# dawa_v5_1.net
KiCad netlist of a schematic drawn in EAGLE
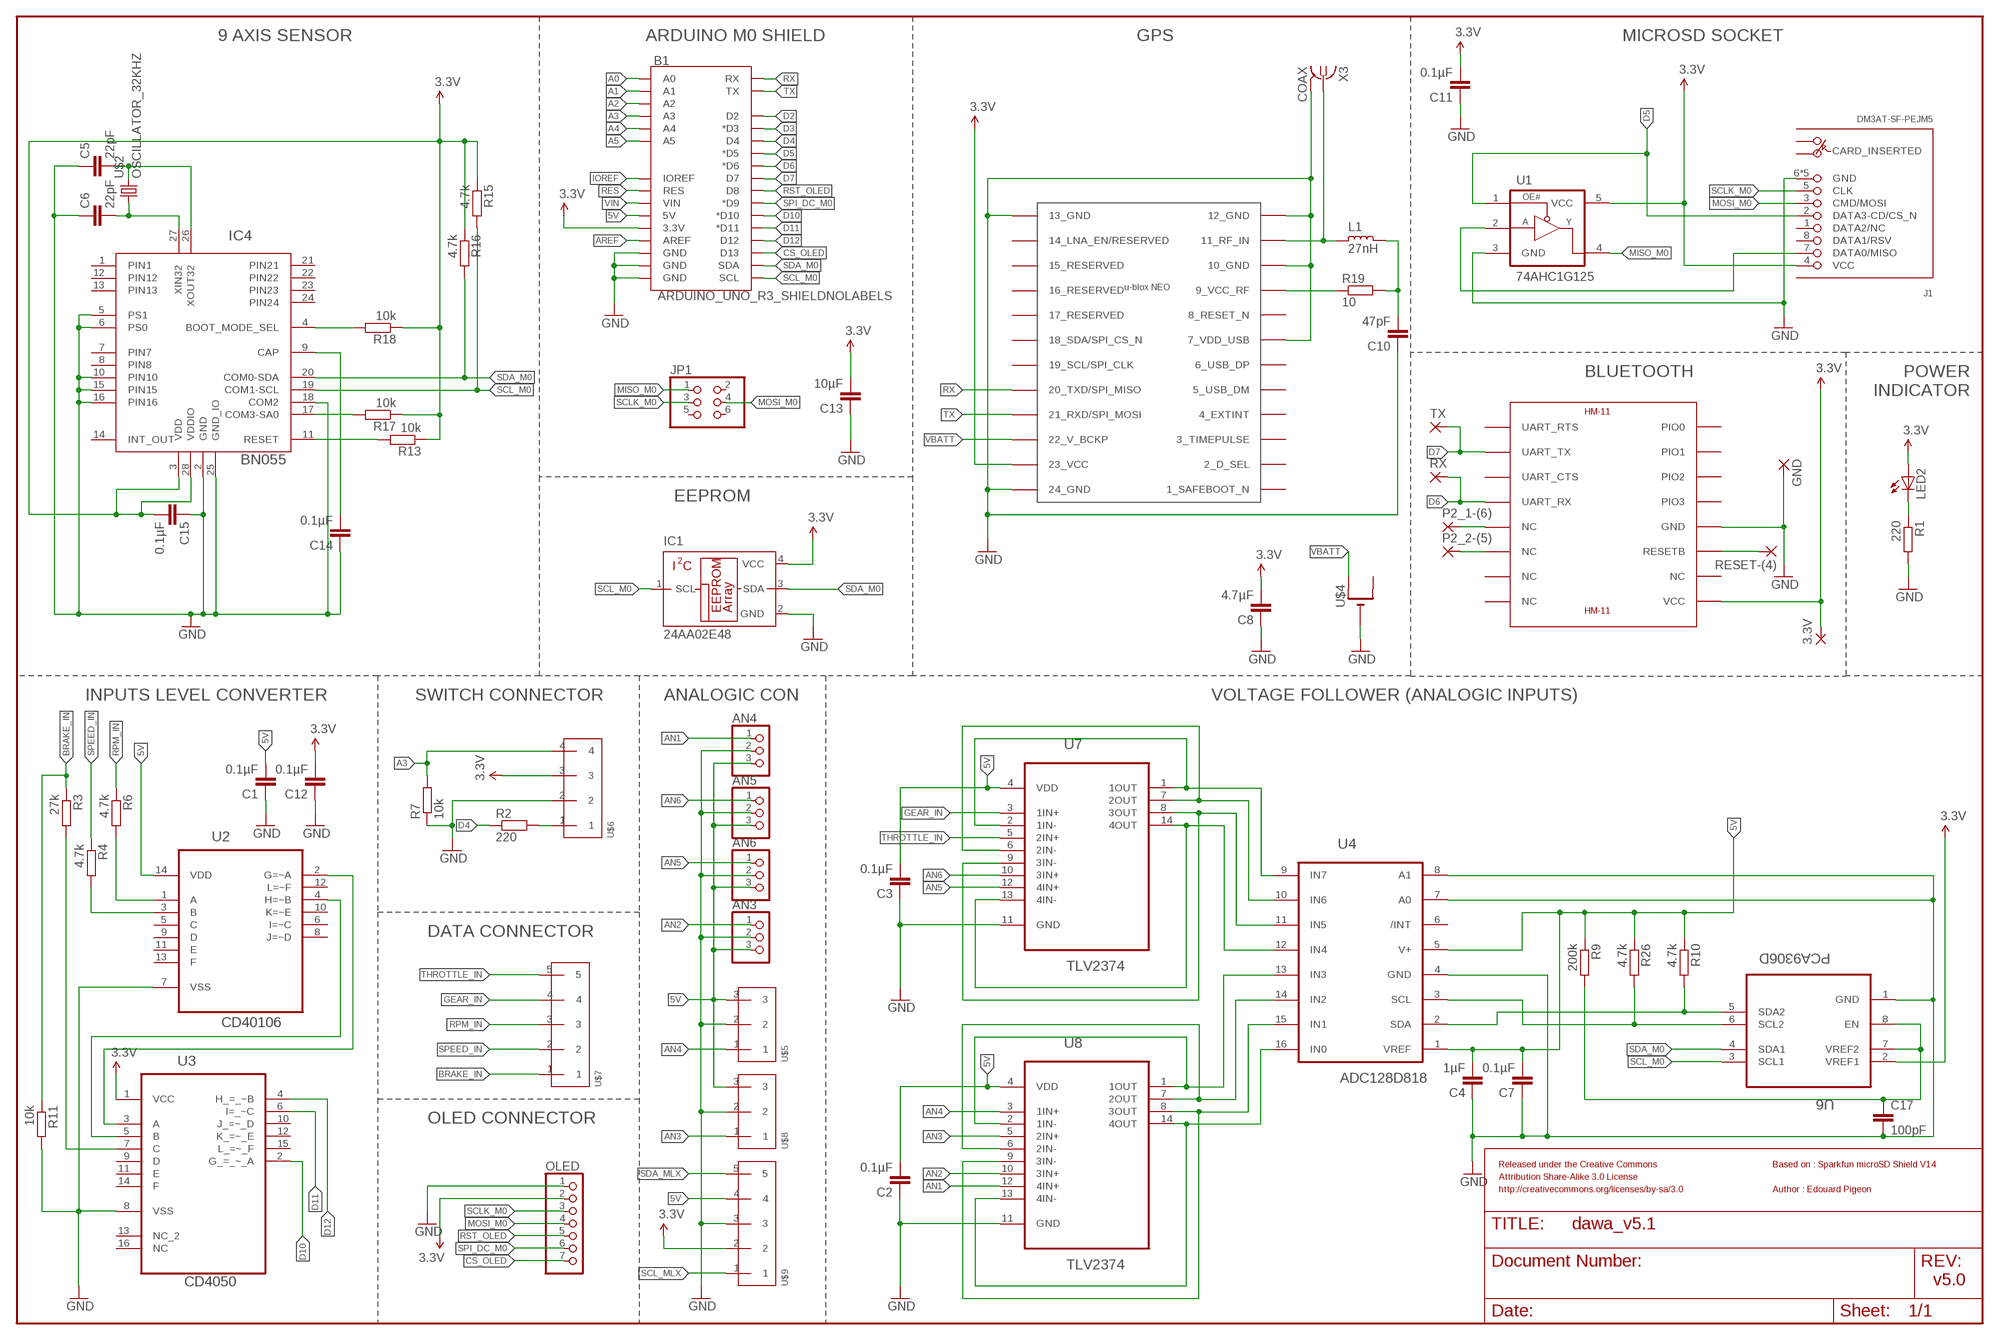
[diagram p0: schematic, sheet 1, part 1 of 2]
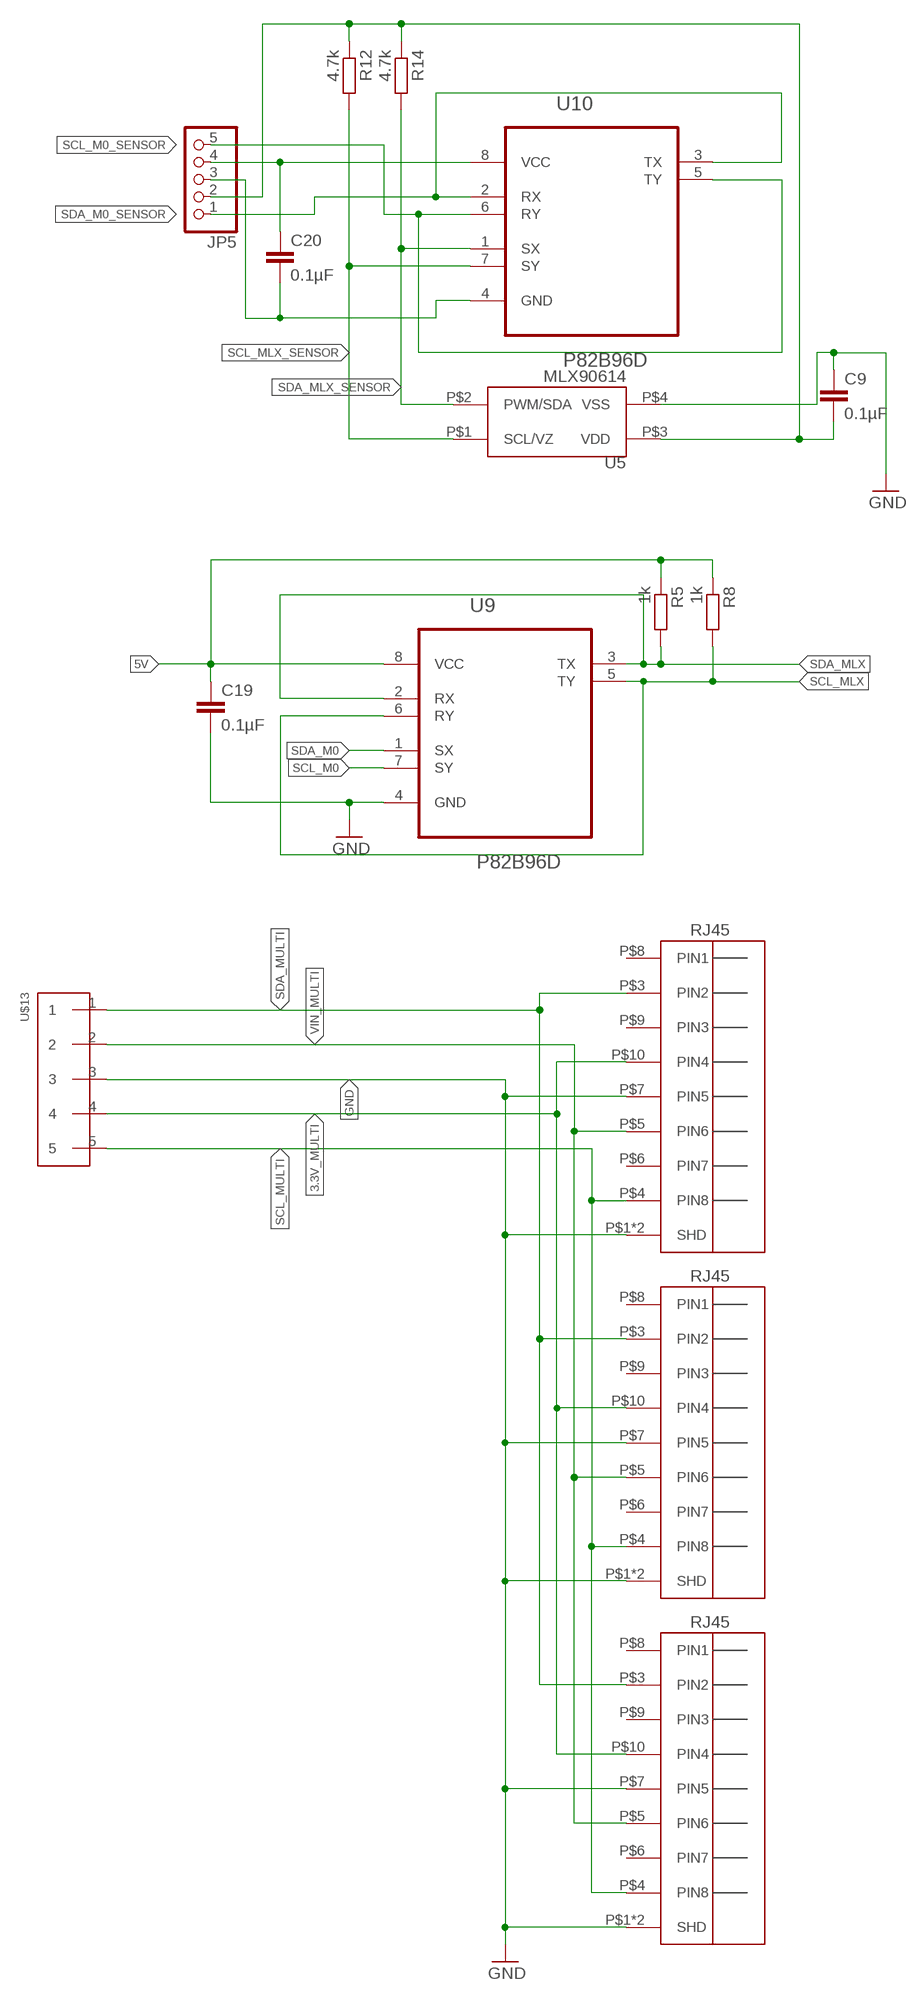
[diagram p1: schematic, sheet 1, part 2 of 2]

(export (version "E")
  (design (tool "Eeschema 10.0.6"))
  (components
    (comp (ref "3.3V")
      (value "WIREPADSMD1,27-254")
      (footprint "eagle-import:SMD1,27-2,54")
      (libsource (lib "eagle-import") (part "WIREPADSMD1,27-254"))
    )
    (comp (ref "AN3")
      (value "PINHD-1X3")
      (footprint "eagle-import:1X03")
      (libsource (lib "eagle-import") (part "PINHD-1X3"))
    )
    (comp (ref "AN4")
      (value "PINHD-1X3")
      (footprint "eagle-import:1X03")
      (libsource (lib "eagle-import") (part "PINHD-1X3"))
    )
    (comp (ref "AN5")
      (value "PINHD-1X3")
      (footprint "eagle-import:1X03")
      (libsource (lib "eagle-import") (part "PINHD-1X3"))
    )
    (comp (ref "AN6")
      (value "PINHD-1X3")
      (footprint "eagle-import:1X03")
      (libsource (lib "eagle-import") (part "PINHD-1X3"))
    )
    (comp (ref "B1")
      (value "ARDUINO_UNO_R3_SHIELDNOLABELS")
      (footprint "eagle-import:UNO_R3_SHIELD_NOLABELS")
      (libsource (lib "eagle-import") (part "ARDUINO_UNO_R3_SHIELDNOLABELS"))
    )
    (comp (ref "C1")
      (value "0.1µF")
      (footprint "eagle-import:C0603")
      (libsource (lib "eagle-import") (part "C-EUC0603"))
    )
    (comp (ref "C2")
      (value "0.1µF")
      (footprint "eagle-import:C0603")
      (libsource (lib "eagle-import") (part "C-EUC0603"))
    )
    (comp (ref "C3")
      (value "0.1µF")
      (footprint "eagle-import:C0603")
      (libsource (lib "eagle-import") (part "C-EUC0603"))
    )
    (comp (ref "C4")
      (value "1µF")
      (footprint "eagle-import:C0603")
      (libsource (lib "eagle-import") (part "C-EUC0603"))
    )
    (comp (ref "C5")
      (value "22pF")
      (footprint "eagle-import:C0603")
      (libsource (lib "eagle-import") (part "C-EUC0603"))
    )
    (comp (ref "C6")
      (value "22pF")
      (footprint "eagle-import:C0603")
      (libsource (lib "eagle-import") (part "C-EUC0603"))
    )
    (comp (ref "C7")
      (value "0.1µF")
      (footprint "eagle-import:C0603")
      (libsource (lib "eagle-import") (part "C-EUC0603"))
    )
    (comp (ref "C8")
      (value "4.7µF")
      (footprint "eagle-import:C0603")
      (libsource (lib "eagle-import") (part "C-EUC0603"))
    )
    (comp (ref "C9")
      (value "0.1µF")
      (footprint "eagle-import:C0603")
      (libsource (lib "eagle-import") (part "C-EUC0603"))
    )
    (comp (ref "C10")
      (value "47pF")
      (footprint "eagle-import:C0603")
      (libsource (lib "eagle-import") (part "C-EUC0603"))
    )
    (comp (ref "C11")
      (value "0.1µF")
      (footprint "eagle-import:C0603")
      (libsource (lib "eagle-import") (part "C-EUC0603"))
    )
    (comp (ref "C12")
      (value "0.1µF")
      (footprint "eagle-import:C0603")
      (libsource (lib "eagle-import") (part "C-EUC0603"))
    )
    (comp (ref "C13")
      (value "10µF")
      (footprint "eagle-import:C0603")
      (libsource (lib "eagle-import") (part "C-EUC0603"))
    )
    (comp (ref "C14")
      (value "0.1µF")
      (footprint "eagle-import:C0603")
      (libsource (lib "eagle-import") (part "C-EUC0603"))
    )
    (comp (ref "C15")
      (value "0.1µF")
      (footprint "eagle-import:C0603")
      (libsource (lib "eagle-import") (part "C-EUC0603"))
    )
    (comp (ref "C17")
      (value "100pF")
      (footprint "eagle-import:C0603")
      (libsource (lib "eagle-import") (part "C-EUC0603"))
    )
    (comp (ref "C19")
      (value "0.1µF")
      (footprint "eagle-import:C0603")
      (libsource (lib "eagle-import") (part "C-EUC0603"))
    )
    (comp (ref "C20")
      (value "0.1µF")
      (footprint "eagle-import:C0603")
      (libsource (lib "eagle-import") (part "C-EUC0603"))
    )
    (comp (ref "GND")
      (value "WIREPADSMD1,27-254")
      (footprint "eagle-import:SMD1,27-2,54")
      (libsource (lib "eagle-import") (part "WIREPADSMD1,27-254"))
    )
    (comp (ref "IC1")
      (value "24AA02E48")
      (footprint "eagle-import:SOT23-5L")
      (fields (field (name "MF") "MICROCHIP") (field (name "MPN") "24AA00T-I/OTG"))
      (libsource (lib "eagle-import") (part "2400OTAA"))
    )
    (comp (ref "IC4")
      (value "BN055")
      (footprint "eagle-import:LGA-28_3.80X5.20_0.5")
      (fields (field (name "PART_NUMBER") "BNO055"))
      (libsource (lib "eagle-import") (part "1658_BNO055"))
    )
    (comp (ref "J1")
      (value "DM3AT-SF-PEJM5")
      (footprint "eagle-import:DM3AT-SF-PEJM5")
      (libsource (lib "eagle-import") (part "DM3AT-SF-PEJM5"))
    )
    (comp (ref "JP1")
      (value "PINHD-2X3")
      (footprint "eagle-import:2X03")
      (libsource (lib "eagle-import") (part "PINHD-2X3"))
    )
    (comp (ref "JP5")
      (value "PINHD-1X5")
      (footprint "eagle-import:1X05")
      (libsource (lib "eagle-import") (part "PINHD-1X5"))
    )
    (comp (ref "L1")
      (value "27nH")
      (footprint "eagle-import:L0603")
      (libsource (lib "eagle-import") (part "L_0603"))
    )
    (comp (ref "LED2")
      (value "LEDCHIPLED_1206")
      (footprint "eagle-import:CHIPLED_1206")
      (libsource (lib "eagle-import") (part "LEDCHIPLED_1206"))
    )
    (comp (ref "OLED")
      (value "PINHD-1X7")
      (footprint "eagle-import:1X07")
      (libsource (lib "eagle-import") (part "PINHD-1X7"))
    )
    (comp (ref "P2_1-(6)")
      (value "WIREPADSMD1,27-254")
      (footprint "eagle-import:SMD1,27-2,54")
      (libsource (lib "eagle-import") (part "WIREPADSMD1,27-254"))
    )
    (comp (ref "P2_2-(5)")
      (value "WIREPADSMD1,27-254")
      (footprint "eagle-import:SMD1,27-2,54")
      (libsource (lib "eagle-import") (part "WIREPADSMD1,27-254"))
    )
    (comp (ref "R1")
      (value "220")
      (footprint "eagle-import:R0603")
      (libsource (lib "eagle-import") (part "R-EU_R0603"))
    )
    (comp (ref "R2")
      (value "220")
      (footprint "eagle-import:R0603")
      (libsource (lib "eagle-import") (part "R-EU_R0603"))
    )
    (comp (ref "R3")
      (value "27k")
      (footprint "eagle-import:R0603")
      (libsource (lib "eagle-import") (part "R-EU_R0603"))
    )
    (comp (ref "R4")
      (value "4.7k")
      (footprint "eagle-import:R0603")
      (libsource (lib "eagle-import") (part "R-EU_R0603"))
    )
    (comp (ref "R5")
      (value "1k")
      (footprint "eagle-import:R0603")
      (libsource (lib "eagle-import") (part "R-EU_R0603"))
    )
    (comp (ref "R6")
      (value "4.7k")
      (footprint "eagle-import:R0603")
      (libsource (lib "eagle-import") (part "R-EU_R0603"))
    )
    (comp (ref "R7")
      (value "10k")
      (footprint "eagle-import:R0603")
      (libsource (lib "eagle-import") (part "R-EU_R0603"))
    )
    (comp (ref "R8")
      (value "1k")
      (footprint "eagle-import:R0603")
      (libsource (lib "eagle-import") (part "R-EU_R0603"))
    )
    (comp (ref "R9")
      (value "200k")
      (footprint "eagle-import:R0603")
      (libsource (lib "eagle-import") (part "R-EU_R0603"))
    )
    (comp (ref "R10")
      (value "4.7k")
      (footprint "eagle-import:R0603")
      (libsource (lib "eagle-import") (part "R-EU_R0603"))
    )
    (comp (ref "R11")
      (value "10k")
      (footprint "eagle-import:R0603")
      (libsource (lib "eagle-import") (part "R-EU_R0603"))
    )
    (comp (ref "R12")
      (value "4.7k")
      (footprint "eagle-import:R0603")
      (libsource (lib "eagle-import") (part "R-EU_R0603"))
    )
    (comp (ref "R13")
      (value "10k")
      (footprint "eagle-import:R0603")
      (libsource (lib "eagle-import") (part "R-EU_R0603"))
    )
    (comp (ref "R14")
      (value "4.7k")
      (footprint "eagle-import:R0603")
      (libsource (lib "eagle-import") (part "R-EU_R0603"))
    )
    (comp (ref "R15")
      (value "4.7k")
      (footprint "eagle-import:R0603")
      (libsource (lib "eagle-import") (part "R-EU_R0603"))
    )
    (comp (ref "R16")
      (value "4.7k")
      (footprint "eagle-import:R0603")
      (libsource (lib "eagle-import") (part "R-EU_R0603"))
    )
    (comp (ref "R17")
      (value "10k")
      (footprint "eagle-import:R0603")
      (libsource (lib "eagle-import") (part "R-EU_R0603"))
    )
    (comp (ref "R18")
      (value "10k")
      (footprint "eagle-import:R0603")
      (libsource (lib "eagle-import") (part "R-EU_R0603"))
    )
    (comp (ref "R19")
      (value "10")
      (footprint "eagle-import:M1206")
      (libsource (lib "eagle-import") (part "R-EU_M1206"))
    )
    (comp (ref "R26")
      (value "4.7k")
      (footprint "eagle-import:R0603")
      (libsource (lib "eagle-import") (part "R-EU_R0603"))
    )
    (comp (ref "RESET-(4)")
      (value "WIREPADSMD1,27-254")
      (footprint "eagle-import:SMD1,27-2,54")
      (libsource (lib "eagle-import") (part "WIREPADSMD1,27-254"))
    )
    (comp (ref "RX")
      (value "WIREPADSMD1,27-254")
      (footprint "eagle-import:SMD1,27-2,54")
      (libsource (lib "eagle-import") (part "WIREPADSMD1,27-254"))
    )
    (comp (ref "TX")
      (value "WIREPADSMD1,27-254")
      (footprint "eagle-import:SMD1,27-2,54")
      (libsource (lib "eagle-import") (part "WIREPADSMD1,27-254"))
    )
    (comp (ref "U$1")
      (value "HM-11")
      (footprint "eagle-import:HM-11")
      (libsource (lib "eagle-import") (part "HM-11"))
    )
    (comp (ref "U$2")
      (value "OSCILLATOR_32KHZ")
      (footprint "eagle-import:OSCILLATOR_SMD")
      (libsource (lib "eagle-import") (part "OSCILLATOR_32KHZ"))
    )
    (comp (ref "U$3")
      (value "NEO-M8")
      (footprint "eagle-import:NEO-M8")
      (libsource (lib "eagle-import") (part "NEO-M8"))
    )
    (comp (ref "U$4")
      (value "CR1220SMT")
      (footprint "eagle-import:CR1220-SMD")
      (libsource (lib "eagle-import") (part "CR1220SMT"))
    )
    (comp (ref "U$5")
      (value "3_PIN_JST-XH-SMD")
      (footprint "eagle-import:3_PIN_JST-XH-SMD")
      (libsource (lib "eagle-import") (part "3_PIN_JST-XH-SMD"))
    )
    (comp (ref "U$6")
      (value "4_PIN_JST-XH-SMD")
      (footprint "eagle-import:4_PIN_JST-XH-SMD")
      (libsource (lib "eagle-import") (part "4_PIN_JST-XH-SMD"))
    )
    (comp (ref "U$7")
      (value "5_PIN_JST-XH-SMD")
      (footprint "eagle-import:5_PIN_JST-XH-SMD")
      (libsource (lib "eagle-import") (part "5_PIN_JST-XH-SMD"))
    )
    (comp (ref "U$8")
      (value "3_PIN_JST-XH-SMD")
      (footprint "eagle-import:3_PIN_JST-XH-SMD")
      (libsource (lib "eagle-import") (part "3_PIN_JST-XH-SMD"))
    )
    (comp (ref "U$9")
      (value "5_PIN_JST-XH-SMD")
      (footprint "eagle-import:5_PIN_JST-XH-SMD")
      (libsource (lib "eagle-import") (part "5_PIN_JST-XH-SMD"))
    )
    (comp (ref "U$10")
      (value "RJ45")
      (footprint "eagle-import:RJ45")
      (libsource (lib "eagle-import") (part "RJ45"))
    )
    (comp (ref "U$11")
      (value "RJ45")
      (footprint "eagle-import:RJ45")
      (libsource (lib "eagle-import") (part "RJ45"))
    )
    (comp (ref "U$12")
      (value "RJ45")
      (footprint "eagle-import:RJ45")
      (libsource (lib "eagle-import") (part "RJ45"))
    )
    (comp (ref "U$13")
      (value "5_PIN_JST-XH-SMD")
      (footprint "eagle-import:5_PIN_JST-XH-SMD")
      (libsource (lib "eagle-import") (part "5_PIN_JST-XH-SMD"))
    )
    (comp (ref "U1")
      (value "74AHC1G125")
      (footprint "eagle-import:SOT23-5")
      (libsource (lib "eagle-import") (part "74AHC1G125DBV"))
    )
    (comp (ref "U2")
      (value "CD40106")
      (footprint "eagle-import:SOP65P640X120-14N")
      (fields (field (name "MPN") "CD40106BPW"))
      (libsource (lib "eagle-import") (part "CD40106BPW"))
    )
    (comp (ref "U3")
      (value "CD4050")
      (footprint "eagle-import:SOP65P640X120-16N")
      (fields (field (name "MPN") "CD4049UBPW"))
      (libsource (lib "eagle-import") (part "CD4049UBPW"))
    )
    (comp (ref "U4")
      (value "ADC128D818")
      (footprint "eagle-import:SOP65P640X120-16N")
      (libsource (lib "eagle-import") (part "ADC128D818"))
    )
    (comp (ref "U5")
      (value "MLX90614")
      (footprint "eagle-import:TO-39")
      (libsource (lib "eagle-import") (part "MLX90614_"))
    )
    (comp (ref "U6")
      (value "PCA9306D")
      (footprint "eagle-import:SOP50P310X90-8N")
      (fields (field (name "MPN") "PCA9306DCUT"))
      (libsource (lib "eagle-import") (part "PCA9306DCUT"))
    )
    (comp (ref "U7")
      (value "TLV2374")
      (footprint "eagle-import:SOP65P640X120-14N")
      (fields (field (name "MPN") "TLV2374IPWR"))
      (libsource (lib "eagle-import") (part "TLV2374IPWR"))
    )
    (comp (ref "U8")
      (value "TLV2374")
      (footprint "eagle-import:SOP65P640X120-14N")
      (fields (field (name "MPN") "TLV2374IPWR"))
      (libsource (lib "eagle-import") (part "TLV2374IPWR"))
    )
    (comp (ref "U9")
      (value "P82B96D")
      (footprint "eagle-import:SOIC127P600X175-8N")
      (libsource (lib "eagle-import") (part "P82B96D"))
    )
    (comp (ref "U10")
      (value "P82B96D")
      (footprint "eagle-import:SOIC127P600X175-8N")
      (libsource (lib "eagle-import") (part "P82B96D"))
    )
    (comp (ref "X3")
      (value "COAX")
      (footprint "eagle-import:MMCX-J-P-X-ST-EM1-MKT")
      (libsource (lib "eagle-import") (part "COAX"))
    )
  )
  (nets
    (net (code "1") (name "3.3V") (class "Default")
      (node (ref "3.3V") (pin "1") (pinfunction "P_1") (pintype "passive"))
      (node (ref "B1") (pin "3.3V") (pinfunction "3.3V_3.3V") (pintype "bidirectional"))
      (node (ref "C11") (pin "2") (pinfunction "2_2") (pintype "passive"))
      (node (ref "C12") (pin "2") (pinfunction "2_2") (pintype "passive"))
      (node (ref "C13") (pin "2") (pinfunction "2_2") (pintype "passive"))
      (node (ref "C15") (pin "2") (pinfunction "2_2") (pintype "passive"))
      (node (ref "C8") (pin "2") (pinfunction "2_2") (pintype "passive"))
      (node (ref "IC1") (pin "4") (pinfunction "VCC_4") (pintype "power_in"))
      (node (ref "IC4") (pin "28") (pinfunction "VDDIO_28") (pintype "power_in"))
      (node (ref "IC4") (pin "3") (pinfunction "VDD_3") (pintype "power_in"))
      (node (ref "J1") (pin "4") (pinfunction "VCC_4") (pintype "bidirectional"))
      (node (ref "LED2") (pin "A") (pinfunction "A_A") (pintype "passive"))
      (node (ref "OLED") (pin "2") (pinfunction "2_2") (pintype "passive"))
      (node (ref "R13") (pin "1") (pinfunction "1_1") (pintype "passive"))
      (node (ref "R15") (pin "1") (pinfunction "1_1") (pintype "passive"))
      (node (ref "R16") (pin "1") (pinfunction "1_1") (pintype "passive"))
      (node (ref "R17") (pin "1") (pinfunction "1_1") (pintype "passive"))
      (node (ref "R18") (pin "1") (pinfunction "1_1") (pintype "passive"))
      (node (ref "U$1") (pin "VCC") (pinfunction "VCC_VCC") (pintype "bidirectional"))
      (node (ref "U$3") (pin "23") (pinfunction "23_VCC_23") (pintype "bidirectional"))
      (node (ref "U$6") (pin "3") (pinfunction "3_3") (pintype "bidirectional"))
      (node (ref "U$9") (pin "2") (pinfunction "2_2") (pintype "bidirectional"))
      (node (ref "U1") (pin "5") (pinfunction "VCC_5") (pintype "power_in"))
      (node (ref "U3") (pin "1") (pinfunction "VCC_1") (pintype "power_in"))
      (node (ref "U6") (pin "2") (pinfunction "VREF1_2") (pintype "power_in"))
    )
    (net (code "2") (name "3.3V_MULTI") (class "Default")
      (node (ref "U$10") (pin "P$10") (pinfunction "PIN4_P$10") (pintype "bidirectional"))
      (node (ref "U$11") (pin "P$10") (pinfunction "PIN4_P$10") (pintype "bidirectional"))
      (node (ref "U$12") (pin "P$10") (pinfunction "PIN4_P$10") (pintype "bidirectional"))
      (node (ref "U$13") (pin "4") (pinfunction "4_4") (pintype "bidirectional"))
    )
    (net (code "3") (name "5V") (class "Default")
      (node (ref "AN3") (pin "3") (pinfunction "3_3") (pintype "passive"))
      (node (ref "AN4") (pin "3") (pinfunction "3_3") (pintype "passive"))
      (node (ref "AN5") (pin "3") (pinfunction "3_3") (pintype "passive"))
      (node (ref "AN6") (pin "3") (pinfunction "3_3") (pintype "passive"))
      (node (ref "B1") (pin "5V") (pinfunction "5V_5V") (pintype "bidirectional"))
      (node (ref "C1") (pin "2") (pinfunction "2_2") (pintype "passive"))
      (node (ref "C19") (pin "1") (pinfunction "1_1") (pintype "passive"))
      (node (ref "C2") (pin "2") (pinfunction "2_2") (pintype "passive"))
      (node (ref "C3") (pin "2") (pinfunction "2_2") (pintype "passive"))
      (node (ref "C4") (pin "2") (pinfunction "2_2") (pintype "passive"))
      (node (ref "C7") (pin "2") (pinfunction "2_2") (pintype "passive"))
      (node (ref "R10") (pin "1") (pinfunction "1_1") (pintype "passive"))
      (node (ref "R26") (pin "1") (pinfunction "1_1") (pintype "passive"))
      (node (ref "R5") (pin "1") (pinfunction "1_1") (pintype "passive"))
      (node (ref "R8") (pin "1") (pinfunction "1_1") (pintype "passive"))
      (node (ref "R9") (pin "1") (pinfunction "1_1") (pintype "passive"))
      (node (ref "U$5") (pin "3") (pinfunction "3_3") (pintype "bidirectional"))
      (node (ref "U$8") (pin "3") (pinfunction "3_3") (pintype "bidirectional"))
      (node (ref "U$9") (pin "4") (pinfunction "4_4") (pintype "bidirectional"))
      (node (ref "U2") (pin "14") (pinfunction "VDD_14") (pintype "power_in"))
      (node (ref "U4") (pin "1") (pinfunction "VREF_1") (pintype "power_in"))
      (node (ref "U4") (pin "5") (pinfunction "V+_5") (pintype "bidirectional"))
      (node (ref "U7") (pin "4") (pinfunction "VDD_4") (pintype "power_in"))
      (node (ref "U8") (pin "4") (pinfunction "VDD_4") (pintype "power_in"))
      (node (ref "U9") (pin "8") (pinfunction "VCC_8") (pintype "power_in"))
    )
    (net (code "4") (name "A0") (class "Default")
      (node (ref "B1") (pin "A0") (pinfunction "A0_A0") (pintype "bidirectional"))
    )
    (net (code "5") (name "A1") (class "Default")
      (node (ref "B1") (pin "A1") (pinfunction "A1_A1") (pintype "bidirectional"))
    )
    (net (code "6") (name "A2") (class "Default")
      (node (ref "B1") (pin "A2") (pinfunction "A2_A2") (pintype "bidirectional"))
    )
    (net (code "7") (name "A3") (class "Default")
      (node (ref "B1") (pin "A3") (pinfunction "A3_A3") (pintype "bidirectional"))
      (node (ref "R7") (pin "2") (pinfunction "2_2") (pintype "passive"))
      (node (ref "U$6") (pin "4") (pinfunction "4_4") (pintype "bidirectional"))
    )
    (net (code "8") (name "A4") (class "Default")
      (node (ref "B1") (pin "A4") (pinfunction "A4_A4") (pintype "bidirectional"))
    )
    (net (code "9") (name "A5") (class "Default")
      (node (ref "B1") (pin "A5") (pinfunction "A5_A5") (pintype "bidirectional"))
    )
    (net (code "10") (name "AN1") (class "Default")
      (node (ref "AN4") (pin "1") (pinfunction "1_1") (pintype "passive"))
      (node (ref "U8") (pin "12") (pinfunction "4IN+_12") (pintype "input"))
    )
    (net (code "11") (name "AN2") (class "Default")
      (node (ref "AN3") (pin "1") (pinfunction "1_1") (pintype "passive"))
      (node (ref "U8") (pin "10") (pinfunction "3IN+_10") (pintype "input"))
    )
    (net (code "12") (name "AN3") (class "Default")
      (node (ref "U$8") (pin "1") (pinfunction "1_1") (pintype "bidirectional"))
      (node (ref "U8") (pin "5") (pinfunction "2IN+_5") (pintype "input"))
    )
    (net (code "13") (name "AN4") (class "Default")
      (node (ref "U$5") (pin "1") (pinfunction "1_1") (pintype "bidirectional"))
      (node (ref "U8") (pin "3") (pinfunction "1IN+_3") (pintype "input"))
    )
    (net (code "14") (name "AN5") (class "Default")
      (node (ref "AN6") (pin "1") (pinfunction "1_1") (pintype "passive"))
      (node (ref "U7") (pin "12") (pinfunction "4IN+_12") (pintype "input"))
    )
    (net (code "15") (name "AN6") (class "Default")
      (node (ref "AN5") (pin "1") (pinfunction "1_1") (pintype "passive"))
      (node (ref "U7") (pin "10") (pinfunction "3IN+_10") (pintype "input"))
    )
    (net (code "16") (name "AREF") (class "Default")
      (node (ref "B1") (pin "AREF") (pinfunction "AREF_AREF") (pintype "bidirectional"))
    )
    (net (code "17") (name "BRAKE_IN") (class "Default")
      (node (ref "R11") (pin "1") (pinfunction "1_1") (pintype "passive"))
      (node (ref "R3") (pin "1") (pinfunction "1_1") (pintype "passive"))
      (node (ref "U$7") (pin "1") (pinfunction "1_1") (pintype "bidirectional"))
    )
    (net (code "18") (name "CS_OLED") (class "Default")
      (node (ref "B1") (pin "D13") (pinfunction "D13_D13") (pintype "bidirectional"))
      (node (ref "OLED") (pin "7") (pinfunction "7_7") (pintype "passive"))
    )
    (net (code "19") (name "D2") (class "Default")
      (node (ref "B1") (pin "D2") (pinfunction "D2_D2") (pintype "bidirectional"))
    )
    (net (code "20") (name "D3") (class "Default")
      (node (ref "B1") (pin "D3") (pinfunction "*D3_D3") (pintype "bidirectional"))
    )
    (net (code "21") (name "D4") (class "Default")
      (node (ref "B1") (pin "D4") (pinfunction "D4_D4") (pintype "bidirectional"))
      (node (ref "R2") (pin "1") (pinfunction "1_1") (pintype "passive"))
    )
    (net (code "22") (name "D5") (class "Default")
      (node (ref "B1") (pin "D5") (pinfunction "*D5_D5") (pintype "bidirectional"))
      (node (ref "J1") (pin "2") (pinfunction "DATA3-CD/CS_N_2") (pintype "bidirectional"))
      (node (ref "U1") (pin "1") (pinfunction "OE#_1") (pintype "input"))
    )
    (net (code "23") (name "D6") (class "Default")
      (node (ref "B1") (pin "D6") (pinfunction "*D6_D6") (pintype "bidirectional"))
      (node (ref "RX") (pin "1") (pinfunction "P_1") (pintype "passive"))
      (node (ref "U$1") (pin "UART_RX") (pinfunction "UART_RX_UART_RX") (pintype "bidirectional"))
    )
    (net (code "24") (name "D7") (class "Default")
      (node (ref "B1") (pin "D7") (pinfunction "D7_D7") (pintype "bidirectional"))
      (node (ref "TX") (pin "1") (pinfunction "P_1") (pintype "passive"))
      (node (ref "U$1") (pin "UART_TX") (pinfunction "UART_TX_UART_TX") (pintype "bidirectional"))
    )
    (net (code "25") (name "D10") (class "Default")
      (node (ref "B1") (pin "D10") (pinfunction "*D10_D10") (pintype "bidirectional"))
      (node (ref "U3") (pin "2") (pinfunction "G_=_~{_A}_2") (pintype "output"))
    )
    (net (code "26") (name "D11") (class "Default")
      (node (ref "B1") (pin "D11") (pinfunction "*D11_D11") (pintype "bidirectional"))
      (node (ref "U3") (pin "6") (pinfunction "I=_~{C}_6") (pintype "output"))
    )
    (net (code "27") (name "D12") (class "Default")
      (node (ref "B1") (pin "D12") (pinfunction "D12_D12") (pintype "bidirectional"))
      (node (ref "U3") (pin "4") (pinfunction "H_=_~{B}_4") (pintype "output"))
    )
    (net (code "28") (name "GEAR_IN") (class "Default")
      (node (ref "U$7") (pin "4") (pinfunction "4_4") (pintype "bidirectional"))
      (node (ref "U7") (pin "3") (pinfunction "1IN+_3") (pintype "input"))
    )
    (net (code "29") (name "GND") (class "Default")
      (node (ref "AN3") (pin "2") (pinfunction "2_2") (pintype "passive"))
      (node (ref "AN4") (pin "2") (pinfunction "2_2") (pintype "passive"))
      (node (ref "AN5") (pin "2") (pinfunction "2_2") (pintype "passive"))
      (node (ref "AN6") (pin "2") (pinfunction "2_2") (pintype "passive"))
      (node (ref "B1") (pin "GND@0") (pinfunction "GND_GND@0") (pintype "bidirectional"))
      (node (ref "B1") (pin "GND@1") (pinfunction "GND_GND@1") (pintype "bidirectional"))
      (node (ref "B1") (pin "GND@2") (pinfunction "GND_GND@2") (pintype "bidirectional"))
      (node (ref "C1") (pin "1") (pinfunction "1_1") (pintype "passive"))
      (node (ref "C10") (pin "1") (pinfunction "1_1") (pintype "passive"))
      (node (ref "C11") (pin "1") (pinfunction "1_1") (pintype "passive"))
      (node (ref "C12") (pin "1") (pinfunction "1_1") (pintype "passive"))
      (node (ref "C13") (pin "1") (pinfunction "1_1") (pintype "passive"))
      (node (ref "C14") (pin "1") (pinfunction "1_1") (pintype "passive"))
      (node (ref "C15") (pin "1") (pinfunction "1_1") (pintype "passive"))
      (node (ref "C17") (pin "2") (pinfunction "2_2") (pintype "passive"))
      (node (ref "C19") (pin "2") (pinfunction "2_2") (pintype "passive"))
      (node (ref "C2") (pin "1") (pinfunction "1_1") (pintype "passive"))
      (node (ref "C3") (pin "1") (pinfunction "1_1") (pintype "passive"))
      (node (ref "C4") (pin "1") (pinfunction "1_1") (pintype "passive"))
      (node (ref "C5") (pin "1") (pinfunction "1_1") (pintype "passive"))
      (node (ref "C6") (pin "1") (pinfunction "1_1") (pintype "passive"))
      (node (ref "C7") (pin "1") (pinfunction "1_1") (pintype "passive"))
      (node (ref "C8") (pin "1") (pinfunction "1_1") (pintype "passive"))
      (node (ref "C9") (pin "1") (pinfunction "1_1") (pintype "passive"))
      (node (ref "GND") (pin "1") (pinfunction "P_1") (pintype "passive"))
      (node (ref "IC1") (pin "2") (pinfunction "GND_2") (pintype "power_in"))
      (node (ref "IC4") (pin "10") (pinfunction "PIN10_10") (pintype "passive"))
      (node (ref "IC4") (pin "15") (pinfunction "PIN15_15") (pintype "passive"))
      (node (ref "IC4") (pin "16") (pinfunction "PIN16_16") (pintype "passive"))
      (node (ref "IC4") (pin "18") (pinfunction "COM2_18") (pintype "bidirectional"))
      (node (ref "IC4") (pin "2") (pinfunction "GND_2") (pintype "power_in"))
      (node (ref "IC4") (pin "25") (pinfunction "GND_IO_25") (pintype "power_in"))
      (node (ref "IC4") (pin "5") (pinfunction "PS1_5") (pintype "input"))
      (node (ref "IC4") (pin "6") (pinfunction "PS0_6") (pintype "input"))
      (node (ref "J1") (pin "6") (pinfunction "GND_6") (pintype "bidirectional"))
      (node (ref "J1") (pin "MOUNT0") (pinfunction "GND_MOUNT0") (pintype "bidirectional"))
      (node (ref "J1") (pin "MOUNT1") (pinfunction "GND_MOUNT1") (pintype "bidirectional"))
      (node (ref "J1") (pin "MOUNT2") (pinfunction "GND_MOUNT2") (pintype "bidirectional"))
      (node (ref "J1") (pin "MOUNT3") (pinfunction "GND_MOUNT3") (pintype "bidirectional"))
      (node (ref "OLED") (pin "1") (pinfunction "1_1") (pintype "passive"))
      (node (ref "R1") (pin "2") (pinfunction "2_2") (pintype "passive"))
      (node (ref "R11") (pin "2") (pinfunction "2_2") (pintype "passive"))
      (node (ref "R7") (pin "1") (pinfunction "1_1") (pintype "passive"))
      (node (ref "U$1") (pin "GND") (pinfunction "GND_GND") (pintype "bidirectional"))
      (node (ref "U$10") (pin "P$1") (pinfunction "SHD_P$1") (pintype "bidirectional"))
      (node (ref "U$10") (pin "P$2") (pinfunction "SHD_P$2") (pintype "bidirectional"))
      (node (ref "U$10") (pin "P$7") (pinfunction "PIN5_P$7") (pintype "bidirectional"))
      (node (ref "U$11") (pin "P$1") (pinfunction "SHD_P$1") (pintype "bidirectional"))
      (node (ref "U$11") (pin "P$2") (pinfunction "SHD_P$2") (pintype "bidirectional"))
      (node (ref "U$11") (pin "P$7") (pinfunction "PIN5_P$7") (pintype "bidirectional"))
      (node (ref "U$12") (pin "P$1") (pinfunction "SHD_P$1") (pintype "bidirectional"))
      (node (ref "U$12") (pin "P$2") (pinfunction "SHD_P$2") (pintype "bidirectional"))
      (node (ref "U$12") (pin "P$7") (pinfunction "PIN5_P$7") (pintype "bidirectional"))
      (node (ref "U$13") (pin "3") (pinfunction "3_3") (pintype "bidirectional"))
      (node (ref "U$3") (pin "10") (pinfunction "10_GND_10") (pintype "bidirectional"))
      (node (ref "U$3") (pin "12") (pinfunction "12_GND_12") (pintype "bidirectional"))
      (node (ref "U$3") (pin "13") (pinfunction "13_GND_13") (pintype "bidirectional"))
      (node (ref "U$3") (pin "24") (pinfunction "24_GND_24") (pintype "bidirectional"))
      (node (ref "U$3") (pin "7") (pinfunction "7_VDD_USB_7") (pintype "bidirectional"))
      (node (ref "U$4") (pin "-") (pinfunction "-_-") (pintype "passive"))
      (node (ref "U$5") (pin "2") (pinfunction "2_2") (pintype "bidirectional"))
      (node (ref "U$6") (pin "2") (pinfunction "2_2") (pintype "bidirectional"))
      (node (ref "U$8") (pin "2") (pinfunction "2_2") (pintype "bidirectional"))
      (node (ref "U$9") (pin "3") (pinfunction "3_3") (pintype "bidirectional"))
      (node (ref "U1") (pin "3") (pinfunction "GND_3") (pintype "power_in"))
      (node (ref "U2") (pin "7") (pinfunction "VSS_7") (pintype "power_in"))
      (node (ref "U3") (pin "8") (pinfunction "VSS_8") (pintype "power_in"))
      (node (ref "U4") (pin "4") (pinfunction "GND_4") (pintype "bidirectional"))
      (node (ref "U4") (pin "7") (pinfunction "A0_7") (pintype "input"))
      (node (ref "U4") (pin "8") (pinfunction "A1_8") (pintype "input"))
      (node (ref "U5") (pin "P$4") (pinfunction "VSS_P$4") (pintype "bidirectional"))
      (node (ref "U6") (pin "1") (pinfunction "GND_1") (pintype "passive"))
      (node (ref "U7") (pin "11") (pinfunction "GND_11") (pintype "power_in"))
      (node (ref "U8") (pin "11") (pinfunction "GND_11") (pintype "power_in"))
      (node (ref "U9") (pin "4") (pinfunction "GND_4") (pintype "passive"))
      (node (ref "X3") (pin "2@1") (pinfunction "GND_2@1") (pintype "power_in"))
    )
    (net (code "30") (name "IOREF") (class "Default")
      (node (ref "B1") (pin "IOREF") (pinfunction "IOREF_IOREF") (pintype "bidirectional"))
    )
    (net (code "31") (name "MISO_M0") (class "Default")
      (node (ref "JP1") (pin "1") (pinfunction "1_1") (pintype "passive"))
      (node (ref "U1") (pin "4") (pinfunction "Y_4") (pintype "output"))
    )
    (net (code "32") (name "MOSI_M0") (class "Default")
      (node (ref "J1") (pin "3") (pinfunction "CMD/MOSI_3") (pintype "bidirectional"))
      (node (ref "JP1") (pin "4") (pinfunction "4_4") (pintype "passive"))
      (node (ref "OLED") (pin "4") (pinfunction "4_4") (pintype "passive"))
    )
    (net (code "33") (name "Net-(C10-Pad2)") (class "Default")
      (node (ref "C10") (pin "2") (pinfunction "2_2") (pintype "passive"))
      (node (ref "L1") (pin "1") (pinfunction "1_1") (pintype "passive"))
      (node (ref "R19") (pin "2") (pinfunction "2_2") (pintype "passive"))
    )
    (net (code "34") (name "Net-(IC4-BOOT_MODE_SEL)") (class "Default")
      (node (ref "IC4") (pin "4") (pinfunction "BOOT_MODE_SEL_4") (pintype "input"))
      (node (ref "R18") (pin "2") (pinfunction "2_2") (pintype "passive"))
    )
    (net (code "35") (name "Net-(IC4-CAP)") (class "Default")
      (node (ref "C14") (pin "2") (pinfunction "2_2") (pintype "passive"))
      (node (ref "IC4") (pin "9") (pinfunction "CAP_9") (pintype "tri_state"))
    )
    (net (code "36") (name "Net-(IC4-COM3-SA0)") (class "Default")
      (node (ref "IC4") (pin "17") (pinfunction "COM3-SA0_17") (pintype "bidirectional"))
      (node (ref "R17") (pin "2") (pinfunction "2_2") (pintype "passive"))
    )
    (net (code "37") (name "Net-(IC4-RESET)") (class "Default")
      (node (ref "IC4") (pin "11") (pinfunction "RESET_11") (pintype "input"))
      (node (ref "R13") (pin "2") (pinfunction "2_2") (pintype "passive"))
    )
    (net (code "38") (name "Net-(IC4-XIN32)") (class "Default")
      (node (ref "C6") (pin "2") (pinfunction "2_2") (pintype "passive"))
      (node (ref "IC4") (pin "27") (pinfunction "XIN32_27") (pintype "bidirectional"))
      (node (ref "U$2") (pin "1") (pinfunction "1_1") (pintype "passive"))
    )
    (net (code "39") (name "Net-(IC4-XOUT32)") (class "Default")
      (node (ref "C5") (pin "2") (pinfunction "2_2") (pintype "passive"))
      (node (ref "IC4") (pin "26") (pinfunction "XOUT32_26") (pintype "output"))
      (node (ref "U$2") (pin "2") (pinfunction "2_2") (pintype "passive"))
    )
    (net (code "40") (name "Net-(J1-DATA0{slash}MISO)") (class "Default")
      (node (ref "J1") (pin "7") (pinfunction "DATA0/MISO_7") (pintype "bidirectional"))
      (node (ref "U1") (pin "2") (pinfunction "A_2") (pintype "input"))
    )
    (net (code "41") (name "Net-(LED2-PadC)") (class "Default")
      (node (ref "LED2") (pin "C") (pinfunction "C_C") (pintype "passive"))
      (node (ref "R1") (pin "1") (pinfunction "1_1") (pintype "passive"))
    )
    (net (code "42") (name "Net-(P2_1-(6)-P)") (class "Default")
      (node (ref "P2_1-(6)") (pin "1") (pinfunction "P_1") (pintype "passive"))
      (node (ref "U$1") (pin "NC@5") (pinfunction "NC_NC@5") (pintype "bidirectional"))
    )
    (net (code "43") (name "Net-(P2_2-(5)-P)") (class "Default")
      (node (ref "P2_2-(5)") (pin "1") (pinfunction "P_1") (pintype "passive"))
      (node (ref "U$1") (pin "NC@6") (pinfunction "NC_NC@6") (pintype "bidirectional"))
    )
    (net (code "44") (name "Net-(R2-Pad2)") (class "Default")
      (node (ref "R2") (pin "2") (pinfunction "2_2") (pintype "passive"))
      (node (ref "U$6") (pin "1") (pinfunction "1_1") (pintype "bidirectional"))
    )
    (net (code "45") (name "Net-(RESET-(4)-P)") (class "Default")
      (node (ref "RESET-(4)") (pin "1") (pinfunction "P_1") (pintype "passive"))
      (node (ref "U$1") (pin "RESETB") (pinfunction "RESETB_RESETB") (pintype "bidirectional"))
    )
    (net (code "46") (name "Net-(U$3-9_VCC_RF)") (class "Default")
      (node (ref "R19") (pin "1") (pinfunction "1_1") (pintype "passive"))
      (node (ref "U$3") (pin "9") (pinfunction "9_VCC_RF_9") (pintype "bidirectional"))
    )
    (net (code "47") (name "Net-(U$3-11_RF_IN)") (class "Default")
      (node (ref "L1") (pin "2") (pinfunction "2_2") (pintype "passive"))
      (node (ref "U$3") (pin "11") (pinfunction "11_RF_IN_11") (pintype "bidirectional"))
      (node (ref "X3") (pin "1") (pinfunction "1_1") (pintype "passive"))
    )
    (net (code "48") (name "Net-(U2-A)") (class "Default")
      (node (ref "R6") (pin "2") (pinfunction "2_2") (pintype "passive"))
      (node (ref "U2") (pin "1") (pinfunction "A_1") (pintype "input"))
    )
    (net (code "49") (name "Net-(U2-B)") (class "Default")
      (node (ref "R4") (pin "2") (pinfunction "2_2") (pintype "passive"))
      (node (ref "U2") (pin "3") (pinfunction "B_3") (pintype "input"))
    )
    (net (code "50") (name "Net-(U2-G=~{A})") (class "Default")
      (node (ref "U2") (pin "2") (pinfunction "G=~{A}_2") (pintype "output"))
      (node (ref "U3") (pin "3") (pinfunction "A_3") (pintype "input"))
    )
    (net (code "51") (name "Net-(U2-H=~{B})") (class "Default")
      (node (ref "U2") (pin "4") (pinfunction "H=~{B}_4") (pintype "output"))
      (node (ref "U3") (pin "5") (pinfunction "B_5") (pintype "input"))
    )
    (net (code "52") (name "Net-(U3-C)") (class "Default")
      (node (ref "R3") (pin "2") (pinfunction "2_2") (pintype "passive"))
      (node (ref "U3") (pin "7") (pinfunction "C_7") (pintype "input"))
    )
    (net (code "53") (name "Net-(U4-IN0)") (class "Default")
      (node (ref "U4") (pin "16") (pinfunction "IN0_16") (pintype "input"))
      (node (ref "U8") (pin "13") (pinfunction "4IN-_13") (pintype "input"))
      (node (ref "U8") (pin "14") (pinfunction "4OUT_14") (pintype "output"))
    )
    (net (code "54") (name "Net-(U4-IN1)") (class "Default")
      (node (ref "U4") (pin "15") (pinfunction "IN1_15") (pintype "input"))
      (node (ref "U8") (pin "8") (pinfunction "3OUT_8") (pintype "output"))
      (node (ref "U8") (pin "9") (pinfunction "3IN-_9") (pintype "input"))
    )
    (net (code "55") (name "Net-(U4-IN2)") (class "Default")
      (node (ref "U4") (pin "14") (pinfunction "IN2_14") (pintype "input"))
      (node (ref "U8") (pin "6") (pinfunction "2IN-_6") (pintype "input"))
      (node (ref "U8") (pin "7") (pinfunction "2OUT_7") (pintype "output"))
    )
    (net (code "56") (name "Net-(U4-IN3)") (class "Default")
      (node (ref "U4") (pin "13") (pinfunction "IN3_13") (pintype "input"))
      (node (ref "U8") (pin "1") (pinfunction "1OUT_1") (pintype "output"))
      (node (ref "U8") (pin "2") (pinfunction "1IN-_2") (pintype "input"))
    )
    (net (code "57") (name "Net-(U4-IN4)") (class "Default")
      (node (ref "U4") (pin "12") (pinfunction "IN4_12") (pintype "input"))
      (node (ref "U7") (pin "13") (pinfunction "4IN-_13") (pintype "input"))
      (node (ref "U7") (pin "14") (pinfunction "4OUT_14") (pintype "output"))
    )
    (net (code "58") (name "Net-(U4-IN5)") (class "Default")
      (node (ref "U4") (pin "11") (pinfunction "IN5_11") (pintype "input"))
      (node (ref "U7") (pin "8") (pinfunction "3OUT_8") (pintype "output"))
      (node (ref "U7") (pin "9") (pinfunction "3IN-_9") (pintype "input"))
    )
    (net (code "59") (name "Net-(U4-IN6)") (class "Default")
      (node (ref "U4") (pin "10") (pinfunction "IN6_10") (pintype "input"))
      (node (ref "U7") (pin "6") (pinfunction "2IN-_6") (pintype "input"))
      (node (ref "U7") (pin "7") (pinfunction "2OUT_7") (pintype "output"))
    )
    (net (code "60") (name "Net-(U4-IN7)") (class "Default")
      (node (ref "U4") (pin "9") (pinfunction "IN7_9") (pintype "input"))
      (node (ref "U7") (pin "1") (pinfunction "1OUT_1") (pintype "output"))
      (node (ref "U7") (pin "2") (pinfunction "1IN-_2") (pintype "input"))
    )
    (net (code "61") (name "Net-(U4-SCL)") (class "Default")
      (node (ref "R26") (pin "2") (pinfunction "2_2") (pintype "passive"))
      (node (ref "U4") (pin "3") (pinfunction "SCL_3") (pintype "bidirectional"))
      (node (ref "U6") (pin "6") (pinfunction "SCL2_6") (pintype "bidirectional"))
    )
    (net (code "62") (name "Net-(U4-SDA)") (class "Default")
      (node (ref "R10") (pin "2") (pinfunction "2_2") (pintype "passive"))
      (node (ref "U4") (pin "2") (pinfunction "SDA_2") (pintype "bidirectional"))
      (node (ref "U6") (pin "5") (pinfunction "SDA2_5") (pintype "bidirectional"))
    )
    (net (code "63") (name "Net-(U5-VDD)") (class "Default")
      (node (ref "C9") (pin "2") (pinfunction "2_2") (pintype "passive"))
      (node (ref "JP5") (pin "2") (pinfunction "2_2") (pintype "passive"))
      (node (ref "R12") (pin "1") (pinfunction "1_1") (pintype "passive"))
      (node (ref "R14") (pin "1") (pinfunction "1_1") (pintype "passive"))
      (node (ref "U5") (pin "P$3") (pinfunction "VDD_P$3") (pintype "bidirectional"))
    )
    (net (code "64") (name "Net-(U6-EN)") (class "Default")
      (node (ref "C17") (pin "1") (pinfunction "1_1") (pintype "passive"))
      (node (ref "R9") (pin "2") (pinfunction "2_2") (pintype "passive"))
      (node (ref "U6") (pin "7") (pinfunction "VREF2_7") (pintype "power_in"))
      (node (ref "U6") (pin "8") (pinfunction "EN_8") (pintype "input"))
    )
    (net (code "65") (name "Net-(U10-GND)") (class "Default")
      (node (ref "C20") (pin "2") (pinfunction "2_2") (pintype "passive"))
      (node (ref "JP5") (pin "3") (pinfunction "3_3") (pintype "passive"))
      (node (ref "U10") (pin "4") (pinfunction "GND_4") (pintype "passive"))
    )
    (net (code "66") (name "Net-(U10-VCC)") (class "Default")
      (node (ref "C20") (pin "1") (pinfunction "1_1") (pintype "passive"))
      (node (ref "JP5") (pin "4") (pinfunction "4_4") (pintype "passive"))
      (node (ref "U10") (pin "8") (pinfunction "VCC_8") (pintype "power_in"))
    )
    (net (code "67") (name "RES") (class "Default")
      (node (ref "B1") (pin "RES") (pinfunction "RES_RES") (pintype "bidirectional"))
    )
    (net (code "68") (name "RPM_IN") (class "Default")
      (node (ref "R6") (pin "1") (pinfunction "1_1") (pintype "passive"))
      (node (ref "U$7") (pin "3") (pinfunction "3_3") (pintype "bidirectional"))
    )
    (net (code "69") (name "RST_OLED") (class "Default")
      (node (ref "B1") (pin "D8") (pinfunction "D8_D8") (pintype "bidirectional"))
      (node (ref "OLED") (pin "5") (pinfunction "5_5") (pintype "passive"))
    )
    (net (code "70") (name "RX") (class "Default")
      (node (ref "B1") (pin "RX") (pinfunction "RX_RX") (pintype "bidirectional"))
      (node (ref "U$3") (pin "20") (pinfunction "20_TXD/SPI_MISO_20") (pintype "bidirectional"))
    )
    (net (code "71") (name "SCLK_M0") (class "Default")
      (node (ref "J1") (pin "5") (pinfunction "CLK_5") (pintype "bidirectional"))
      (node (ref "JP1") (pin "3") (pinfunction "3_3") (pintype "passive"))
      (node (ref "OLED") (pin "3") (pinfunction "3_3") (pintype "passive"))
    )
    (net (code "72") (name "SCL_M0") (class "Default")
      (node (ref "B1") (pin "SCL") (pinfunction "SCL_SCL") (pintype "bidirectional"))
      (node (ref "IC1") (pin "1") (pinfunction "SCL_1") (pintype "input"))
      (node (ref "IC4") (pin "19") (pinfunction "COM1-SCL_19") (pintype "bidirectional"))
      (node (ref "R15") (pin "2") (pinfunction "2_2") (pintype "passive"))
      (node (ref "U6") (pin "3") (pinfunction "SCL1_3") (pintype "bidirectional"))
      (node (ref "U9") (pin "7") (pinfunction "SY_7") (pintype "input"))
    )
    (net (code "73") (name "SCL_M0_SENSOR") (class "Default")
      (node (ref "JP5") (pin "5") (pinfunction "5_5") (pintype "passive"))
      (node (ref "U10") (pin "5") (pinfunction "TY_5") (pintype "output"))
      (node (ref "U10") (pin "6") (pinfunction "RY_6") (pintype "input"))
    )
    (net (code "74") (name "SCL_MLX") (class "Default")
      (node (ref "R8") (pin "2") (pinfunction "2_2") (pintype "passive"))
      (node (ref "U$9") (pin "1") (pinfunction "1_1") (pintype "bidirectional"))
      (node (ref "U9") (pin "5") (pinfunction "TY_5") (pintype "output"))
      (node (ref "U9") (pin "6") (pinfunction "RY_6") (pintype "input"))
    )
    (net (code "75") (name "SCL_MLX_SENSOR") (class "Default")
      (node (ref "R12") (pin "2") (pinfunction "2_2") (pintype "passive"))
      (node (ref "U10") (pin "7") (pinfunction "SY_7") (pintype "input"))
      (node (ref "U5") (pin "P$1") (pinfunction "SCL/VZ_P$1") (pintype "bidirectional"))
    )
    (net (code "76") (name "SCL_MULTI") (class "Default")
      (node (ref "U$10") (pin "P$4") (pinfunction "PIN8_P$4") (pintype "bidirectional"))
      (node (ref "U$11") (pin "P$4") (pinfunction "PIN8_P$4") (pintype "bidirectional"))
      (node (ref "U$12") (pin "P$4") (pinfunction "PIN8_P$4") (pintype "bidirectional"))
      (node (ref "U$13") (pin "5") (pinfunction "5_5") (pintype "bidirectional"))
    )
    (net (code "77") (name "SDA_M0") (class "Default")
      (node (ref "B1") (pin "SDA") (pinfunction "SDA_SDA") (pintype "bidirectional"))
      (node (ref "IC1") (pin "3") (pinfunction "SDA_3") (pintype "bidirectional"))
      (node (ref "IC4") (pin "20") (pinfunction "COM0-SDA_20") (pintype "bidirectional"))
      (node (ref "R16") (pin "2") (pinfunction "2_2") (pintype "passive"))
      (node (ref "U6") (pin "4") (pinfunction "SDA1_4") (pintype "bidirectional"))
      (node (ref "U9") (pin "1") (pinfunction "SX_1") (pintype "input"))
    )
    (net (code "78") (name "SDA_M0_SENSOR") (class "Default")
      (node (ref "JP5") (pin "1") (pinfunction "1_1") (pintype "passive"))
      (node (ref "U10") (pin "2") (pinfunction "RX_2") (pintype "input"))
      (node (ref "U10") (pin "3") (pinfunction "TX_3") (pintype "output"))
    )
    (net (code "79") (name "SDA_MLX") (class "Default")
      (node (ref "R5") (pin "2") (pinfunction "2_2") (pintype "passive"))
      (node (ref "U$9") (pin "5") (pinfunction "5_5") (pintype "bidirectional"))
      (node (ref "U9") (pin "2") (pinfunction "RX_2") (pintype "input"))
      (node (ref "U9") (pin "3") (pinfunction "TX_3") (pintype "output"))
    )
    (net (code "80") (name "SDA_MLX_SENSOR") (class "Default")
      (node (ref "R14") (pin "2") (pinfunction "2_2") (pintype "passive"))
      (node (ref "U10") (pin "1") (pinfunction "SX_1") (pintype "input"))
      (node (ref "U5") (pin "P$2") (pinfunction "PWM/SDA_P$2") (pintype "bidirectional"))
    )
    (net (code "81") (name "SDA_MULTI") (class "Default")
      (node (ref "U$10") (pin "P$3") (pinfunction "PIN2_P$3") (pintype "bidirectional"))
      (node (ref "U$11") (pin "P$3") (pinfunction "PIN2_P$3") (pintype "bidirectional"))
      (node (ref "U$12") (pin "P$3") (pinfunction "PIN2_P$3") (pintype "bidirectional"))
      (node (ref "U$13") (pin "1") (pinfunction "1_1") (pintype "bidirectional"))
    )
    (net (code "82") (name "SPEED_IN") (class "Default")
      (node (ref "R4") (pin "1") (pinfunction "1_1") (pintype "passive"))
      (node (ref "U$7") (pin "2") (pinfunction "2_2") (pintype "bidirectional"))
    )
    (net (code "83") (name "SPI_DC_M0") (class "Default")
      (node (ref "B1") (pin "D9") (pinfunction "*D9_D9") (pintype "bidirectional"))
      (node (ref "OLED") (pin "6") (pinfunction "6_6") (pintype "passive"))
    )
    (net (code "84") (name "THROTTLE_IN") (class "Default")
      (node (ref "U$7") (pin "5") (pinfunction "5_5") (pintype "bidirectional"))
      (node (ref "U7") (pin "5") (pinfunction "2IN+_5") (pintype "input"))
    )
    (net (code "85") (name "TX") (class "Default")
      (node (ref "B1") (pin "TX") (pinfunction "TX_TX") (pintype "bidirectional"))
      (node (ref "U$3") (pin "21") (pinfunction "21_RXD/SPI_MOSI_21") (pintype "bidirectional"))
    )
    (net (code "86") (name "VBATT") (class "Default")
      (node (ref "U$3") (pin "22") (pinfunction "22_V_BCKP_22") (pintype "bidirectional"))
      (node (ref "U$4") (pin "+$1") (pinfunction "+_+$1") (pintype "passive"))
    )
    (net (code "87") (name "VIN") (class "Default")
      (node (ref "B1") (pin "VIN") (pinfunction "VIN_VIN") (pintype "bidirectional"))
    )
    (net (code "88") (name "VIN_MULTI") (class "Default")
      (node (ref "U$10") (pin "P$5") (pinfunction "PIN6_P$5") (pintype "bidirectional"))
      (node (ref "U$11") (pin "P$5") (pinfunction "PIN6_P$5") (pintype "bidirectional"))
      (node (ref "U$12") (pin "P$5") (pinfunction "PIN6_P$5") (pintype "bidirectional"))
      (node (ref "U$13") (pin "2") (pinfunction "2_2") (pintype "bidirectional"))
    )
    (net (code "89") (name "unconnected-(IC4-INT_OUT-Pad14)") (class "Default")
      (node (ref "IC4") (pin "14") (pinfunction "INT_OUT_14") (pintype "output"))
    )
    (net (code "90") (name "unconnected-(IC4-PIN1-Pad1)") (class "Default")
      (node (ref "IC4") (pin "1") (pinfunction "PIN1_1") (pintype "no_connect"))
    )
    (net (code "91") (name "unconnected-(IC4-PIN7-Pad7)") (class "Default")
      (node (ref "IC4") (pin "7") (pinfunction "PIN7_7") (pintype "tri_state"))
    )
    (net (code "92") (name "unconnected-(IC4-PIN8-Pad8)") (class "Default")
      (node (ref "IC4") (pin "8") (pinfunction "PIN8_8") (pintype "tri_state"))
    )
    (net (code "93") (name "unconnected-(IC4-PIN12-Pad12)") (class "Default")
      (node (ref "IC4") (pin "12") (pinfunction "PIN12_12") (pintype "passive"))
    )
    (net (code "94") (name "unconnected-(IC4-PIN13-Pad13)") (class "Default")
      (node (ref "IC4") (pin "13") (pinfunction "PIN13_13") (pintype "passive"))
    )
    (net (code "95") (name "unconnected-(IC4-PIN21-Pad21)") (class "Default")
      (node (ref "IC4") (pin "21") (pinfunction "PIN21_21") (pintype "passive"))
    )
    (net (code "96") (name "unconnected-(IC4-PIN22-Pad22)") (class "Default")
      (node (ref "IC4") (pin "22") (pinfunction "PIN22_22") (pintype "passive"))
    )
    (net (code "97") (name "unconnected-(IC4-PIN23-Pad23)") (class "Default")
      (node (ref "IC4") (pin "23") (pinfunction "PIN23_23") (pintype "passive"))
    )
    (net (code "98") (name "unconnected-(IC4-PIN24-Pad24)") (class "Default")
      (node (ref "IC4") (pin "24") (pinfunction "PIN24_24") (pintype "passive"))
    )
    (net (code "99") (name "unconnected-(J1-DATA1{slash}RSV-Pad8)") (class "Default")
      (node (ref "J1") (pin "8") (pinfunction "DATA1/RSV_8") (pintype "bidirectional"))
    )
    (net (code "100") (name "unconnected-(J1-DATA2{slash}NC-Pad1)") (class "Default")
      (node (ref "J1") (pin "1") (pinfunction "DATA2/NC_1") (pintype "bidirectional"))
    )
    (net (code "101") (name "unconnected-(J1-PadA)") (class "Default")
      (node (ref "J1") (pin "A") (pinfunction "A_A") (pintype "bidirectional"))
    )
    (net (code "102") (name "unconnected-(J1-PadB)") (class "Default")
      (node (ref "J1") (pin "B") (pinfunction "B_B") (pintype "bidirectional"))
    )
    (net (code "103") (name "unconnected-(JP1-Pad2)") (class "Default")
      (node (ref "JP1") (pin "2") (pinfunction "2_2") (pintype "passive"))
    )
    (net (code "104") (name "unconnected-(JP1-Pad5)") (class "Default")
      (node (ref "JP1") (pin "5") (pinfunction "5_5") (pintype "passive"))
    )
    (net (code "105") (name "unconnected-(JP1-Pad6)") (class "Default")
      (node (ref "JP1") (pin "6") (pinfunction "6_6") (pintype "passive"))
    )
    (net (code "106") (name "unconnected-(U$1-NC-PadNC@7)") (class "Default")
      (node (ref "U$1") (pin "NC@7") (pinfunction "NC_NC@7") (pintype "bidirectional"))
    )
    (net (code "107") (name "unconnected-(U$1-NC-PadNC@8)") (class "Default")
      (node (ref "U$1") (pin "NC@8") (pinfunction "NC_NC@8") (pintype "bidirectional"))
    )
    (net (code "108") (name "unconnected-(U$1-NC-PadNC@10)") (class "Default")
      (node (ref "U$1") (pin "NC@10") (pinfunction "NC_NC@10") (pintype "bidirectional"))
    )
    (net (code "109") (name "unconnected-(U$1-PadPIO0)") (class "Default")
      (node (ref "U$1") (pin "PIO0") (pinfunction "PIO0_PIO0") (pintype "bidirectional"))
    )
    (net (code "110") (name "unconnected-(U$1-PadPIO1)") (class "Default")
      (node (ref "U$1") (pin "PIO1") (pinfunction "PIO1_PIO1") (pintype "bidirectional"))
    )
    (net (code "111") (name "unconnected-(U$1-PadPIO2)") (class "Default")
      (node (ref "U$1") (pin "PIO2") (pinfunction "PIO2_PIO2") (pintype "bidirectional"))
    )
    (net (code "112") (name "unconnected-(U$1-PadPIO3)") (class "Default")
      (node (ref "U$1") (pin "PIO3") (pinfunction "PIO3_PIO3") (pintype "bidirectional"))
    )
    (net (code "113") (name "unconnected-(U$1-PadUART_CTS)") (class "Default")
      (node (ref "U$1") (pin "UART_CTS") (pinfunction "UART_CTS_UART_CTS") (pintype "bidirectional"))
    )
    (net (code "114") (name "unconnected-(U$1-PadUART_RTS)") (class "Default")
      (node (ref "U$1") (pin "UART_RTS") (pinfunction "UART_RTS_UART_RTS") (pintype "bidirectional"))
    )
    (net (code "115") (name "unconnected-(U$3-1_SAFEBOOT_N-Pad1)") (class "Default")
      (node (ref "U$3") (pin "1") (pinfunction "1_SAFEBOOT_N_1") (pintype "bidirectional"))
    )
    (net (code "116") (name "unconnected-(U$3-2_D_SEL-Pad2)") (class "Default")
      (node (ref "U$3") (pin "2") (pinfunction "2_D_SEL_2") (pintype "bidirectional"))
    )
    (net (code "117") (name "unconnected-(U$3-3_TIMEPULSE-Pad3)") (class "Default")
      (node (ref "U$3") (pin "3") (pinfunction "3_TIMEPULSE_3") (pintype "bidirectional"))
    )
    (net (code "118") (name "unconnected-(U$3-4_EXTINT-Pad4)") (class "Default")
      (node (ref "U$3") (pin "4") (pinfunction "4_EXTINT_4") (pintype "bidirectional"))
    )
    (net (code "119") (name "unconnected-(U$3-5_USB_DM-Pad5)") (class "Default")
      (node (ref "U$3") (pin "5") (pinfunction "5_USB_DM_5") (pintype "bidirectional"))
    )
    (net (code "120") (name "unconnected-(U$3-6_USB_DP-Pad6)") (class "Default")
      (node (ref "U$3") (pin "6") (pinfunction "6_USB_DP_6") (pintype "bidirectional"))
    )
    (net (code "121") (name "unconnected-(U$3-8_RESET_N-Pad8)") (class "Default")
      (node (ref "U$3") (pin "8") (pinfunction "8_RESET_N_8") (pintype "bidirectional"))
    )
    (net (code "122") (name "unconnected-(U$3-14_LNA_EN{slash}RESERVED-Pad14)") (class "Default")
      (node (ref "U$3") (pin "14") (pinfunction "14_LNA_EN/RESERVED_14") (pintype "bidirectional"))
    )
    (net (code "123") (name "unconnected-(U$3-15_RESERVED-Pad15)") (class "Default")
      (node (ref "U$3") (pin "15") (pinfunction "15_RESERVED_15") (pintype "bidirectional"))
    )
    (net (code "124") (name "unconnected-(U$3-16_RESERVED-Pad16)") (class "Default")
      (node (ref "U$3") (pin "16") (pinfunction "16_RESERVED_16") (pintype "bidirectional"))
    )
    (net (code "125") (name "unconnected-(U$3-17_RESERVED-Pad17)") (class "Default")
      (node (ref "U$3") (pin "17") (pinfunction "17_RESERVED_17") (pintype "bidirectional"))
    )
    (net (code "126") (name "unconnected-(U$3-18_SDA{slash}SPI_CS_N-Pad18)") (class "Default")
      (node (ref "U$3") (pin "18") (pinfunction "18_SDA/SPI_CS_N_18") (pintype "bidirectional"))
    )
    (net (code "127") (name "unconnected-(U$3-19_SCL{slash}SPI_CLK-Pad19)") (class "Default")
      (node (ref "U$3") (pin "19") (pinfunction "19_SCL/SPI_CLK_19") (pintype "bidirectional"))
    )
    (net (code "128") (name "unconnected-(U$4-+1-Pad+$2)") (class "Default")
      (node (ref "U$4") (pin "+$2") (pinfunction "+1_+$2") (pintype "passive"))
    )
    (net (code "129") (name "unconnected-(U$10-PIN1-PadP$8)") (class "Default")
      (node (ref "U$10") (pin "P$8") (pinfunction "PIN1_P$8") (pintype "bidirectional"))
    )
    (net (code "130") (name "unconnected-(U$10-PIN3-PadP$9)") (class "Default")
      (node (ref "U$10") (pin "P$9") (pinfunction "PIN3_P$9") (pintype "bidirectional"))
    )
    (net (code "131") (name "unconnected-(U$10-PIN7-PadP$6)") (class "Default")
      (node (ref "U$10") (pin "P$6") (pinfunction "PIN7_P$6") (pintype "bidirectional"))
    )
    (net (code "132") (name "unconnected-(U$11-PIN1-PadP$8)") (class "Default")
      (node (ref "U$11") (pin "P$8") (pinfunction "PIN1_P$8") (pintype "bidirectional"))
    )
    (net (code "133") (name "unconnected-(U$11-PIN3-PadP$9)") (class "Default")
      (node (ref "U$11") (pin "P$9") (pinfunction "PIN3_P$9") (pintype "bidirectional"))
    )
    (net (code "134") (name "unconnected-(U$11-PIN7-PadP$6)") (class "Default")
      (node (ref "U$11") (pin "P$6") (pinfunction "PIN7_P$6") (pintype "bidirectional"))
    )
    (net (code "135") (name "unconnected-(U$12-PIN1-PadP$8)") (class "Default")
      (node (ref "U$12") (pin "P$8") (pinfunction "PIN1_P$8") (pintype "bidirectional"))
    )
    (net (code "136") (name "unconnected-(U$12-PIN3-PadP$9)") (class "Default")
      (node (ref "U$12") (pin "P$9") (pinfunction "PIN3_P$9") (pintype "bidirectional"))
    )
    (net (code "137") (name "unconnected-(U$12-PIN7-PadP$6)") (class "Default")
      (node (ref "U$12") (pin "P$6") (pinfunction "PIN7_P$6") (pintype "bidirectional"))
    )
    (net (code "138") (name "unconnected-(U2-C-Pad5)") (class "Default")
      (node (ref "U2") (pin "5") (pinfunction "C_5") (pintype "input"))
    )
    (net (code "139") (name "unconnected-(U2-D-Pad9)") (class "Default")
      (node (ref "U2") (pin "9") (pinfunction "D_9") (pintype "input"))
    )
    (net (code "140") (name "unconnected-(U2-E-Pad11)") (class "Default")
      (node (ref "U2") (pin "11") (pinfunction "E_11") (pintype "input"))
    )
    (net (code "141") (name "unconnected-(U2-F-Pad13)") (class "Default")
      (node (ref "U2") (pin "13") (pinfunction "F_13") (pintype "input"))
    )
    (net (code "142") (name "unconnected-(U2-I=~{C}-Pad6)") (class "Default")
      (node (ref "U2") (pin "6") (pinfunction "I=~{C}_6") (pintype "output"))
    )
    (net (code "143") (name "unconnected-(U2-J=~{D}-Pad8)") (class "Default")
      (node (ref "U2") (pin "8") (pinfunction "J=~{D}_8") (pintype "output"))
    )
    (net (code "144") (name "unconnected-(U2-K=~{E}-Pad10)") (class "Default")
      (node (ref "U2") (pin "10") (pinfunction "K=~{E}_10") (pintype "output"))
    )
    (net (code "145") (name "unconnected-(U2-L=~{F}-Pad12)") (class "Default")
      (node (ref "U2") (pin "12") (pinfunction "L=~{F}_12") (pintype "output"))
    )
    (net (code "146") (name "unconnected-(U3-D-Pad9)") (class "Default")
      (node (ref "U3") (pin "9") (pinfunction "D_9") (pintype "input"))
    )
    (net (code "147") (name "unconnected-(U3-E-Pad11)") (class "Default")
      (node (ref "U3") (pin "11") (pinfunction "E_11") (pintype "input"))
    )
    (net (code "148") (name "unconnected-(U3-F-Pad14)") (class "Default")
      (node (ref "U3") (pin "14") (pinfunction "F_14") (pintype "input"))
    )
    (net (code "149") (name "unconnected-(U3-J_=~{_D}-Pad10)") (class "Default")
      (node (ref "U3") (pin "10") (pinfunction "J_=~{_D}_10") (pintype "output"))
    )
    (net (code "150") (name "unconnected-(U3-K_=~{_E}-Pad12)") (class "Default")
      (node (ref "U3") (pin "12") (pinfunction "K_=~{_E}_12") (pintype "output"))
    )
    (net (code "151") (name "unconnected-(U3-L_=~{_F}-Pad15)") (class "Default")
      (node (ref "U3") (pin "15") (pinfunction "L_=~{_F}_15") (pintype "output"))
    )
    (net (code "152") (name "unconnected-(U3-NC-Pad16)") (class "Default")
      (node (ref "U3") (pin "16") (pinfunction "NC_16") (pintype "no_connect"))
    )
    (net (code "153") (name "unconnected-(U3-NC_2-Pad13)") (class "Default")
      (node (ref "U3") (pin "13") (pinfunction "NC_2_13") (pintype "no_connect"))
    )
    (net (code "154") (name "unconnected-(U4-{slash}INT-Pad6)") (class "Default")
      (node (ref "U4") (pin "6") (pinfunction "/INT_6") (pintype "output"))
    )
  )
)
